# MainBoard.net
KiCad netlist of a schematic drawn in Altium Designer
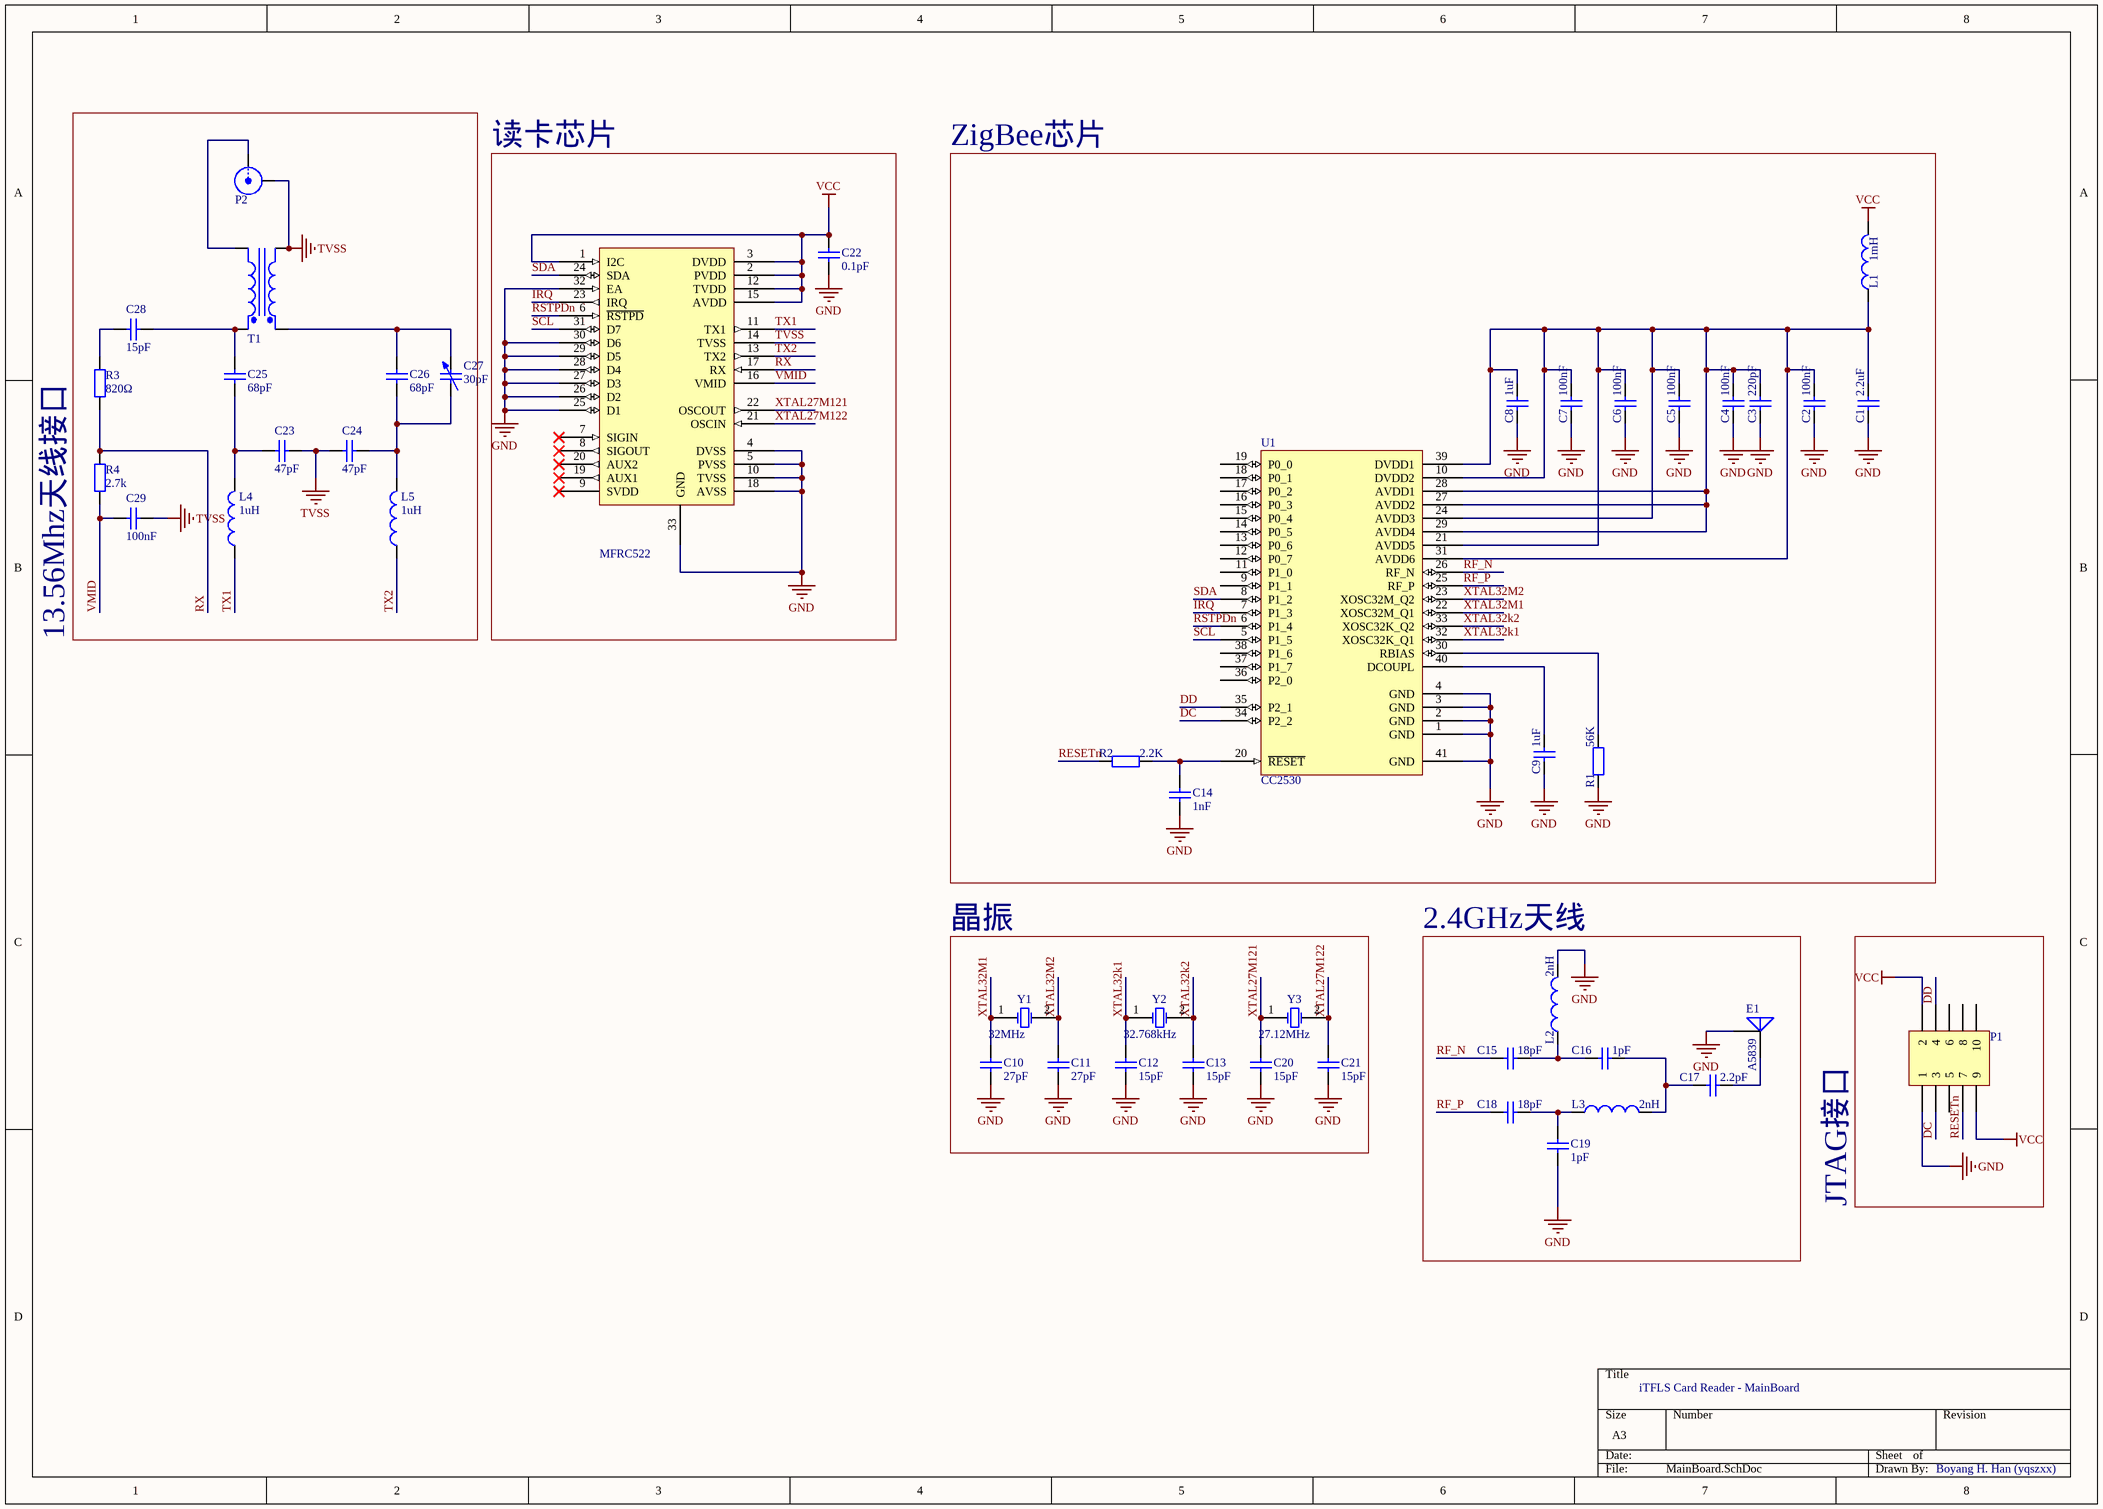
[diagram p0: MainBoard.SchDoc]

(export (version "E")
  (design (tool "Eeschema 10.0.6"))
  (components
    (comp (ref "C1")
      (value "2.2uF")
      (footprint "0603")
      (description "Capacitor")
      (fields (field (name "Comment") "Cap") (field (name "PUBLISHER") "Altium Limited"))
      (libsource (lib "Miscellaneous Devices") (part "Cap"))
    )
    (comp (ref "C2")
      (value "100nF")
      (footprint "0603")
      (description "Capacitor")
      (fields (field (name "Comment") "Cap") (field (name "PUBLISHER") "Altium Limited"))
      (libsource (lib "Miscellaneous Devices") (part "Cap"))
    )
    (comp (ref "C3")
      (value "220pF")
      (footprint "0603")
      (description "Capacitor")
      (fields (field (name "Comment") "Cap") (field (name "PUBLISHER") "Altium Limited"))
      (libsource (lib "Miscellaneous Devices") (part "Cap"))
    )
    (comp (ref "C4")
      (value "100nF")
      (footprint "0603")
      (description "Capacitor")
      (fields (field (name "Comment") "Cap") (field (name "PUBLISHER") "Altium Limited"))
      (libsource (lib "Miscellaneous Devices") (part "Cap"))
    )
    (comp (ref "C5")
      (value "100nF")
      (footprint "0603")
      (description "Capacitor")
      (fields (field (name "Comment") "Cap") (field (name "PUBLISHER") "Altium Limited"))
      (libsource (lib "Miscellaneous Devices") (part "Cap"))
    )
    (comp (ref "C6")
      (value "100nF")
      (footprint "0603")
      (description "Capacitor")
      (fields (field (name "Comment") "Cap") (field (name "PUBLISHER") "Altium Limited"))
      (libsource (lib "Miscellaneous Devices") (part "Cap"))
    )
    (comp (ref "C7")
      (value "100nF")
      (footprint "0603")
      (description "Capacitor")
      (fields (field (name "Comment") "Cap") (field (name "PUBLISHER") "Altium Limited"))
      (libsource (lib "Miscellaneous Devices") (part "Cap"))
    )
    (comp (ref "C8")
      (value "1uF")
      (footprint "0603")
      (description "Capacitor")
      (fields (field (name "Comment") "Cap") (field (name "PUBLISHER") "Altium Limited"))
      (libsource (lib "Miscellaneous Devices") (part "Cap"))
    )
    (comp (ref "C9")
      (value "1uF")
      (footprint "0603")
      (description "Capacitor")
      (fields (field (name "Comment") "Cap") (field (name "PUBLISHER") "Altium Limited"))
      (libsource (lib "Miscellaneous Devices") (part "Cap"))
    )
    (comp (ref "C10")
      (value "27pF")
      (footprint "0603")
      (description "Capacitor")
      (fields (field (name "Comment") "Cap") (field (name "PUBLISHER") "Altium Limited"))
      (libsource (lib "Miscellaneous Devices") (part "Cap"))
    )
    (comp (ref "C11")
      (value "27pF")
      (footprint "0603")
      (description "Capacitor")
      (fields (field (name "Comment") "Cap") (field (name "PUBLISHER") "Altium Limited"))
      (libsource (lib "Miscellaneous Devices") (part "Cap"))
    )
    (comp (ref "C12")
      (value "15pF")
      (footprint "0603")
      (description "Capacitor")
      (fields (field (name "Comment") "Cap") (field (name "PUBLISHER") "Altium Limited"))
      (libsource (lib "Miscellaneous Devices") (part "Cap"))
    )
    (comp (ref "C13")
      (value "15pF")
      (footprint "0603")
      (description "Capacitor")
      (fields (field (name "Comment") "Cap") (field (name "PUBLISHER") "Altium Limited"))
      (libsource (lib "Miscellaneous Devices") (part "Cap"))
    )
    (comp (ref "C14")
      (value "1nF")
      (footprint "0603")
      (description "Capacitor")
      (fields (field (name "Comment") "Cap") (field (name "PUBLISHER") "Altium Limited"))
      (libsource (lib "Miscellaneous Devices") (part "Cap"))
    )
    (comp (ref "C15")
      (value "18pF")
      (footprint "0603")
      (description "Capacitor")
      (fields (field (name "Comment") "Cap") (field (name "PUBLISHER") "Altium Limited"))
      (libsource (lib "Miscellaneous Devices") (part "Cap"))
    )
    (comp (ref "C16")
      (value "1pF")
      (footprint "0603")
      (description "Capacitor")
      (fields (field (name "Comment") "Cap") (field (name "PUBLISHER") "Altium Limited"))
      (libsource (lib "Miscellaneous Devices") (part "Cap"))
    )
    (comp (ref "C17")
      (value "2.2pF")
      (footprint "0603")
      (description "Capacitor")
      (fields (field (name "Comment") "Cap") (field (name "PUBLISHER") "Altium Limited"))
      (libsource (lib "Miscellaneous Devices") (part "Cap"))
    )
    (comp (ref "C18")
      (value "18pF")
      (footprint "0603")
      (description "Capacitor")
      (fields (field (name "Comment") "Cap") (field (name "PUBLISHER") "Altium Limited"))
      (libsource (lib "Miscellaneous Devices") (part "Cap"))
    )
    (comp (ref "C19")
      (value "1pF")
      (footprint "0603")
      (description "Capacitor")
      (fields (field (name "Comment") "Cap") (field (name "PUBLISHER") "Altium Limited"))
      (libsource (lib "Miscellaneous Devices") (part "Cap"))
    )
    (comp (ref "C20")
      (value "15pF")
      (footprint "0603")
      (description "Capacitor")
      (fields (field (name "Comment") "Cap") (field (name "PUBLISHER") "Altium Limited"))
      (libsource (lib "Miscellaneous Devices") (part "Cap"))
    )
    (comp (ref "C21")
      (value "15pF")
      (footprint "0603")
      (description "Capacitor")
      (fields (field (name "Comment") "Cap") (field (name "PUBLISHER") "Altium Limited"))
      (libsource (lib "Miscellaneous Devices") (part "Cap"))
    )
    (comp (ref "C22")
      (value "0.1pF")
      (footprint "0603")
      (description "Capacitor")
      (fields (field (name "Comment") "Cap") (field (name "PUBLISHER") "Altium Limited"))
      (libsource (lib "Miscellaneous Devices") (part "Cap"))
    )
    (comp (ref "C23")
      (value "47pF")
      (footprint "0603")
      (description "Capacitor")
      (fields (field (name "Comment") "Cap") (field (name "PUBLISHER") "Altium Limited"))
      (libsource (lib "Miscellaneous Devices") (part "Cap"))
    )
    (comp (ref "C24")
      (value "47pF")
      (footprint "0603")
      (description "Capacitor")
      (fields (field (name "Comment") "Cap") (field (name "PUBLISHER") "Altium Limited"))
      (libsource (lib "Miscellaneous Devices") (part "Cap"))
    )
    (comp (ref "C25")
      (value "68pF")
      (footprint "0603")
      (description "Capacitor")
      (fields (field (name "Comment") "Cap") (field (name "PUBLISHER") "Altium Limited"))
      (libsource (lib "Miscellaneous Devices") (part "Cap"))
    )
    (comp (ref "C26")
      (value "68pF")
      (footprint "0603")
      (description "Capacitor")
      (fields (field (name "Comment") "Cap") (field (name "PUBLISHER") "Altium Limited"))
      (libsource (lib "Miscellaneous Devices") (part "Cap"))
    )
    (comp (ref "C27")
      (value "30pF")
      (footprint "4x4VC")
      (description "Variable or Adjustable Capacitor")
      (fields (field (name "Comment") "Cap Var") (field (name "PUBLISHER") "Altium Limited"))
      (libsource (lib "Miscellaneous Devices") (part "Cap Var"))
    )
    (comp (ref "C28")
      (value "15pF")
      (footprint "0603")
      (description "Capacitor")
      (fields (field (name "Comment") "Cap") (field (name "PUBLISHER") "Altium Limited"))
      (libsource (lib "Miscellaneous Devices") (part "Cap"))
    )
    (comp (ref "C29")
      (value "100nF")
      (footprint "0603")
      (description "Capacitor")
      (fields (field (name "Comment") "Cap") (field (name "PUBLISHER") "Altium Limited"))
      (libsource (lib "Miscellaneous Devices") (part "Cap"))
    )
    (comp (ref "E1") (value "A5839") (footprint "A5839") (libsource (lib "A5839") (part "A5839")))
    (comp (ref "L1")
      (value "1mH")
      (footprint "0603")
      (description "Inductor")
      (fields (field (name "PUBLISHER") "Altium Limited"))
      (libsource (lib "Miscellaneous Devices") (part "Inductor"))
    )
    (comp (ref "L2")
      (value "2nH")
      (footprint "0603")
      (description "Inductor")
      (fields (field (name "PUBLISHER") "Altium Limited"))
      (libsource (lib "Miscellaneous Devices") (part "Inductor"))
    )
    (comp (ref "L3")
      (value "2nH")
      (footprint "0603")
      (description "Inductor")
      (fields (field (name "PUBLISHER") "Altium Limited"))
      (libsource (lib "Miscellaneous Devices") (part "Inductor"))
    )
    (comp (ref "L4")
      (value "1uH")
      (footprint "0603")
      (description "Inductor")
      (fields (field (name "PUBLISHER") "Altium Limited"))
      (libsource (lib "Miscellaneous Devices") (part "Inductor"))
    )
    (comp (ref "L5")
      (value "1uH")
      (footprint "0603")
      (description "Inductor")
      (fields (field (name "PUBLISHER") "Altium Limited"))
      (libsource (lib "Miscellaneous Devices") (part "Inductor"))
    )
    (comp (ref "P1")
      (value "Header 5X2")
      (footprint "HDR2X5")
      (description "Header, 5-Pin, Dual row")
      (fields (field (name "PUBLISHER") "Altium Limited"))
      (libsource (lib "Miscellaneous Connectors") (part "Header 5X2"))
    )
    (comp (ref "P2")
      (value "U.FL")
      (footprint "U.FL")
      (description "SMB Straight Connector")
      (fields (field (name "PUBLISHER") "Altium Limited"))
      (libsource (lib "Miscellaneous Connectors") (part "SMB"))
    )
    (comp (ref "R1")
      (value "56K")
      (footprint "0603")
      (description "Resistor")
      (fields (field (name "Comment") "Res2") (field (name "PUBLISHER") "Altium Limited"))
      (libsource (lib "Miscellaneous Devices") (part "Res2"))
    )
    (comp (ref "R2")
      (value "2.2K")
      (footprint "0603")
      (description "Resistor")
      (fields (field (name "Comment") "Res2") (field (name "PUBLISHER") "Altium Limited"))
      (libsource (lib "") (part "Res2_1"))
    )
    (comp (ref "R3")
      (value "820Ω")
      (footprint "0603")
      (description "Resistor")
      (fields (field (name "Comment") "Res2") (field (name "PUBLISHER") "Altium Limited"))
      (libsource (lib "Miscellaneous Devices") (part "Res2"))
    )
    (comp (ref "R4")
      (value "2.7k")
      (footprint "0603")
      (description "Resistor")
      (fields (field (name "Comment") "Res2") (field (name "PUBLISHER") "Altium Limited"))
      (libsource (lib "Miscellaneous Devices") (part "Res2"))
    )
    (comp (ref "T1")
      (value "1812WBT-3")
      (footprint "1812WBT-3")
      (libsource (lib "Coilcraft 1812WBT-3") (part "1812WBT-3"))
    )
    (comp (ref "U1") (value "CC2530") (footprint "QFN40") (libsource (lib "CC2530") (part "CC2530")))
    (comp (ref "U2") (value "MFRC522") (footprint "QFN32") (libsource (lib "MFRC522") (part "MFRC522")))
    (comp (ref "Y1")
      (value "32MHz")
      (footprint "XTAL3225")
      (description "Crystal Oscillator")
      (fields (field (name "Comment") "XTAL") (field (name "PUBLISHER") "Altium Limited"))
      (libsource (lib "Miscellaneous Devices") (part "XTAL"))
    )
    (comp (ref "Y2")
      (value "32.768kHz")
      (footprint "XTAL3215")
      (description "Crystal Oscillator")
      (fields (field (name "Comment") "XTAL") (field (name "PUBLISHER") "Altium Limited"))
      (libsource (lib "Miscellaneous Devices") (part "XTAL"))
    )
    (comp (ref "Y3")
      (value "27.12MHz")
      (footprint "XTAL3225")
      (description "Crystal Oscillator")
      (fields (field (name "Comment") "XTAL") (field (name "PUBLISHER") "Altium Limited"))
      (libsource (lib "Miscellaneous Devices") (part "XTAL"))
    )
  )
  (nets
    (net (code "1") (name "/DC") (class "Default")
      (node (ref "P1") (pin "3") (pinfunction "3_3") (pintype "passive"))
      (node (ref "U1") (pin "34") (pinfunction "P2_2_34") (pintype "bidirectional"))
    )
    (net (code "2") (name "/DD") (class "Default")
      (node (ref "P1") (pin "4") (pinfunction "4_4") (pintype "passive"))
      (node (ref "U1") (pin "35") (pinfunction "P2_1_35") (pintype "bidirectional"))
    )
    (net (code "3") (name "/IRQ") (class "Default")
      (node (ref "U1") (pin "7") (pinfunction "P1_3_7") (pintype "bidirectional"))
      (node (ref "U2") (pin "23") (pinfunction "IRQ_23") (pintype "output"))
    )
    (net (code "4") (name "/RESETn") (class "Default")
      (node (ref "P1") (pin "7") (pinfunction "7_7") (pintype "passive"))
      (node (ref "R2") (pin "1") (pinfunction "1_1") (pintype "passive"))
    )
    (net (code "5") (name "/RF_N") (class "Default")
      (node (ref "C15") (pin "1") (pinfunction "1_1") (pintype "passive"))
      (node (ref "U1") (pin "26") (pinfunction "RF_N_26") (pintype "bidirectional"))
    )
    (net (code "6") (name "/RF_P") (class "Default")
      (node (ref "C18") (pin "1") (pinfunction "1_1") (pintype "passive"))
      (node (ref "U1") (pin "25") (pinfunction "RF_P_25") (pintype "bidirectional"))
    )
    (net (code "7") (name "/RSTPDn") (class "Default")
      (node (ref "U1") (pin "6") (pinfunction "P1_4_6") (pintype "bidirectional"))
      (node (ref "U2") (pin "6") (pinfunction "~{RSTPD}_6") (pintype "input"))
    )
    (net (code "8") (name "/RX") (class "Default")
      (node (ref "R3") (pin "1") (pinfunction "1_1") (pintype "passive"))
      (node (ref "R4") (pin "2") (pinfunction "2_2") (pintype "passive"))
      (node (ref "U2") (pin "17") (pinfunction "RX_17") (pintype "input"))
    )
    (net (code "9") (name "/SCL") (class "Default")
      (node (ref "U1") (pin "5") (pinfunction "P1_5_5") (pintype "bidirectional"))
      (node (ref "U2") (pin "31") (pinfunction "D7_31") (pintype "bidirectional"))
    )
    (net (code "10") (name "/SDA") (class "Default")
      (node (ref "U1") (pin "8") (pinfunction "P1_2_8") (pintype "bidirectional"))
      (node (ref "U2") (pin "24") (pinfunction "SDA_24") (pintype "bidirectional"))
    )
    (net (code "11") (name "/TX1") (class "Default")
      (node (ref "L4") (pin "1") (pinfunction "1_1") (pintype "passive"))
      (node (ref "U2") (pin "11") (pinfunction "TX1_11") (pintype "output"))
    )
    (net (code "12") (name "/TX2") (class "Default")
      (node (ref "L5") (pin "1") (pinfunction "1_1") (pintype "passive"))
      (node (ref "U2") (pin "13") (pinfunction "TX2_13") (pintype "output"))
    )
    (net (code "13") (name "/VMID") (class "Default")
      (node (ref "C29") (pin "2") (pinfunction "2_2") (pintype "passive"))
      (node (ref "R4") (pin "1") (pinfunction "1_1") (pintype "passive"))
      (node (ref "U2") (pin "16") (pinfunction "VMID_16") (pintype "power_in"))
    )
    (net (code "14") (name "/XTAL27M121") (class "Default")
      (node (ref "C20") (pin "2") (pinfunction "2_2") (pintype "passive"))
      (node (ref "U2") (pin "22") (pinfunction "OSCOUT_22") (pintype "output"))
      (node (ref "Y3") (pin "1") (pinfunction "OSC1_1") (pintype "passive"))
    )
    (net (code "15") (name "/XTAL27M122") (class "Default")
      (node (ref "C21") (pin "2") (pinfunction "2_2") (pintype "passive"))
      (node (ref "U2") (pin "21") (pinfunction "OSCIN_21") (pintype "input"))
      (node (ref "Y3") (pin "2") (pinfunction "OSC2_2") (pintype "passive"))
    )
    (net (code "16") (name "/XTAL32M1") (class "Default")
      (node (ref "C10") (pin "2") (pinfunction "2_2") (pintype "passive"))
      (node (ref "U1") (pin "22") (pinfunction "XOSC32M_Q1_22") (pintype "bidirectional"))
      (node (ref "Y1") (pin "1") (pinfunction "OSC1_1") (pintype "passive"))
    )
    (net (code "17") (name "/XTAL32M2") (class "Default")
      (node (ref "C11") (pin "2") (pinfunction "2_2") (pintype "passive"))
      (node (ref "U1") (pin "23") (pinfunction "XOSC32M_Q2_23") (pintype "bidirectional"))
      (node (ref "Y1") (pin "2") (pinfunction "OSC2_2") (pintype "passive"))
    )
    (net (code "18") (name "/XTAL32k1") (class "Default")
      (node (ref "C12") (pin "2") (pinfunction "2_2") (pintype "passive"))
      (node (ref "U1") (pin "32") (pinfunction "XOSC32K_Q1_32") (pintype "bidirectional"))
      (node (ref "Y2") (pin "1") (pinfunction "OSC1_1") (pintype "passive"))
    )
    (net (code "19") (name "/XTAL32k2") (class "Default")
      (node (ref "C13") (pin "2") (pinfunction "2_2") (pintype "passive"))
      (node (ref "U1") (pin "33") (pinfunction "XOSC32K_Q2_33") (pintype "bidirectional"))
      (node (ref "Y2") (pin "2") (pinfunction "OSC2_2") (pintype "passive"))
    )
    (net (code "20") (name "GND") (class "Default")
      (node (ref "C1") (pin "1") (pinfunction "1_1") (pintype "passive"))
      (node (ref "C10") (pin "1") (pinfunction "1_1") (pintype "passive"))
      (node (ref "C11") (pin "1") (pinfunction "1_1") (pintype "passive"))
      (node (ref "C12") (pin "1") (pinfunction "1_1") (pintype "passive"))
      (node (ref "C13") (pin "1") (pinfunction "1_1") (pintype "passive"))
      (node (ref "C14") (pin "1") (pinfunction "1_1") (pintype "passive"))
      (node (ref "C19") (pin "1") (pinfunction "1_1") (pintype "passive"))
      (node (ref "C2") (pin "1") (pinfunction "1_1") (pintype "passive"))
      (node (ref "C20") (pin "1") (pinfunction "1_1") (pintype "passive"))
      (node (ref "C21") (pin "1") (pinfunction "1_1") (pintype "passive"))
      (node (ref "C22") (pin "1") (pinfunction "1_1") (pintype "passive"))
      (node (ref "C3") (pin "1") (pinfunction "1_1") (pintype "passive"))
      (node (ref "C4") (pin "1") (pinfunction "1_1") (pintype "passive"))
      (node (ref "C5") (pin "1") (pinfunction "1_1") (pintype "passive"))
      (node (ref "C6") (pin "1") (pinfunction "1_1") (pintype "passive"))
      (node (ref "C7") (pin "1") (pinfunction "1_1") (pintype "passive"))
      (node (ref "C8") (pin "1") (pinfunction "1_1") (pintype "passive"))
      (node (ref "C9") (pin "1") (pinfunction "1_1") (pintype "passive"))
      (node (ref "E1") (pin "2") (pinfunction "GND_2") (pintype "passive"))
      (node (ref "L2") (pin "2") (pinfunction "2_2") (pintype "passive"))
      (node (ref "P1") (pin "1") (pinfunction "1_1") (pintype "passive"))
      (node (ref "R1") (pin "1") (pinfunction "1_1") (pintype "passive"))
      (node (ref "U1") (pin "1") (pinfunction "GND_1") (pintype "power_in"))
      (node (ref "U1") (pin "2") (pinfunction "GND_2") (pintype "power_in"))
      (node (ref "U1") (pin "3") (pinfunction "GND_3") (pintype "power_in"))
      (node (ref "U1") (pin "4") (pinfunction "GND_4") (pintype "power_in"))
      (node (ref "U1") (pin "41") (pinfunction "GND_41") (pintype "power_in"))
      (node (ref "U2") (pin "10") (pinfunction "TVSS_10") (pintype "power_in"))
      (node (ref "U2") (pin "18") (pinfunction "AVSS_18") (pintype "power_in"))
      (node (ref "U2") (pin "25") (pinfunction "D1_25") (pintype "bidirectional"))
      (node (ref "U2") (pin "26") (pinfunction "D2_26") (pintype "bidirectional"))
      (node (ref "U2") (pin "27") (pinfunction "D3_27") (pintype "bidirectional"))
      (node (ref "U2") (pin "28") (pinfunction "D4_28") (pintype "bidirectional"))
      (node (ref "U2") (pin "29") (pinfunction "D5_29") (pintype "bidirectional"))
      (node (ref "U2") (pin "30") (pinfunction "D6_30") (pintype "bidirectional"))
      (node (ref "U2") (pin "32") (pinfunction "EA_32") (pintype "input"))
      (node (ref "U2") (pin "33") (pinfunction "GND_33") (pintype "power_in"))
      (node (ref "U2") (pin "4") (pinfunction "DVSS_4") (pintype "power_in"))
      (node (ref "U2") (pin "5") (pinfunction "PVSS_5") (pintype "power_in"))
    )
    (net (code "21") (name "Net-(C15-Pad2)") (class "Default")
      (node (ref "C15") (pin "2") (pinfunction "2_2") (pintype "passive"))
      (node (ref "C16") (pin "1") (pinfunction "1_1") (pintype "passive"))
      (node (ref "L2") (pin "1") (pinfunction "1_1") (pintype "passive"))
    )
    (net (code "22") (name "Net-(C16-Pad2)") (class "Default")
      (node (ref "C16") (pin "2") (pinfunction "2_2") (pintype "passive"))
      (node (ref "C17") (pin "1") (pinfunction "1_1") (pintype "passive"))
      (node (ref "L3") (pin "2") (pinfunction "2_2") (pintype "passive"))
    )
    (net (code "23") (name "Net-(C18-Pad2)") (class "Default")
      (node (ref "C18") (pin "2") (pinfunction "2_2") (pintype "passive"))
      (node (ref "C19") (pin "2") (pinfunction "2_2") (pintype "passive"))
      (node (ref "L3") (pin "1") (pinfunction "1_1") (pintype "passive"))
    )
    (net (code "24") (name "Net-(C23-Pad2)") (class "Default")
      (node (ref "C23") (pin "2") (pinfunction "2_2") (pintype "passive"))
      (node (ref "C25") (pin "1") (pinfunction "1_1") (pintype "passive"))
      (node (ref "L4") (pin "2") (pinfunction "2_2") (pintype "passive"))
    )
    (net (code "25") (name "Net-(C24-Pad1)") (class "Default")
      (node (ref "C24") (pin "1") (pinfunction "1_1") (pintype "passive"))
      (node (ref "C26") (pin "1") (pinfunction "1_1") (pintype "passive"))
      (node (ref "C27") (pin "1") (pinfunction "1_1") (pintype "passive"))
      (node (ref "L5") (pin "2") (pinfunction "2_2") (pintype "passive"))
    )
    (net (code "26") (name "Net-(C28-Pad2)") (class "Default")
      (node (ref "C28") (pin "2") (pinfunction "2_2") (pintype "passive"))
      (node (ref "R3") (pin "2") (pinfunction "2_2") (pintype "passive"))
    )
    (net (code "27") (name "Net-(E1-FEED)") (class "Default")
      (node (ref "C17") (pin "2") (pinfunction "2_2") (pintype "passive"))
      (node (ref "E1") (pin "1") (pinfunction "FEED_1") (pintype "passive"))
    )
    (net (code "28") (name "Net-(P2-X)") (class "Default")
      (node (ref "P2") (pin "1") (pinfunction "X_1") (pintype "passive"))
      (node (ref "T1") (pin "3") (pinfunction "Sec-_3") (pintype "passive"))
    )
    (net (code "29") (name "Net-(T1-Pri+)") (class "Default")
      (node (ref "C26") (pin "2") (pinfunction "2_2") (pintype "passive"))
      (node (ref "C27") (pin "2") (pinfunction "2_2") (pintype "passive"))
      (node (ref "T1") (pin "1") (pinfunction "Pri+_1") (pintype "passive"))
    )
    (net (code "30") (name "Net-(T1-Sec+)") (class "Default")
      (node (ref "C25") (pin "2") (pinfunction "2_2") (pintype "passive"))
      (node (ref "C28") (pin "1") (pinfunction "1_1") (pintype "passive"))
      (node (ref "T1") (pin "4") (pinfunction "Sec+_4") (pintype "passive"))
    )
    (net (code "31") (name "Net-(U1-AVDD1)") (class "Default")
      (node (ref "C1") (pin "2") (pinfunction "2_2") (pintype "passive"))
      (node (ref "C2") (pin "2") (pinfunction "2_2") (pintype "passive"))
      (node (ref "C3") (pin "2") (pinfunction "2_2") (pintype "passive"))
      (node (ref "C4") (pin "2") (pinfunction "2_2") (pintype "passive"))
      (node (ref "C5") (pin "2") (pinfunction "2_2") (pintype "passive"))
      (node (ref "C6") (pin "2") (pinfunction "2_2") (pintype "passive"))
      (node (ref "C7") (pin "2") (pinfunction "2_2") (pintype "passive"))
      (node (ref "C8") (pin "2") (pinfunction "2_2") (pintype "passive"))
      (node (ref "L1") (pin "1") (pinfunction "1_1") (pintype "passive"))
      (node (ref "U1") (pin "10") (pinfunction "DVDD2_10") (pintype "power_in"))
      (node (ref "U1") (pin "21") (pinfunction "AVDD5_21") (pintype "power_in"))
      (node (ref "U1") (pin "24") (pinfunction "AVDD3_24") (pintype "power_in"))
      (node (ref "U1") (pin "27") (pinfunction "AVDD2_27") (pintype "power_in"))
      (node (ref "U1") (pin "28") (pinfunction "AVDD1_28") (pintype "power_in"))
      (node (ref "U1") (pin "29") (pinfunction "AVDD4_29") (pintype "power_in"))
      (node (ref "U1") (pin "31") (pinfunction "AVDD6_31") (pintype "power_in"))
      (node (ref "U1") (pin "39") (pinfunction "DVDD1_39") (pintype "power_in"))
    )
    (net (code "32") (name "Net-(U1-DCOUPL)") (class "Default")
      (node (ref "C9") (pin "2") (pinfunction "2_2") (pintype "passive"))
      (node (ref "U1") (pin "40") (pinfunction "DCOUPL_40") (pintype "power_in"))
    )
    (net (code "33") (name "Net-(U1-RBIAS)") (class "Default")
      (node (ref "R1") (pin "2") (pinfunction "2_2") (pintype "passive"))
      (node (ref "U1") (pin "30") (pinfunction "RBIAS_30") (pintype "bidirectional"))
    )
    (net (code "34") (name "Net-(U1-~{RESET})") (class "Default")
      (node (ref "C14") (pin "2") (pinfunction "2_2") (pintype "passive"))
      (node (ref "R2") (pin "2") (pinfunction "2_2") (pintype "passive"))
      (node (ref "U1") (pin "20") (pinfunction "~{RESET}_20") (pintype "input"))
    )
    (net (code "35") (name "TVSS") (class "Default")
      (node (ref "C23") (pin "1") (pinfunction "1_1") (pintype "passive"))
      (node (ref "C24") (pin "2") (pinfunction "2_2") (pintype "passive"))
      (node (ref "C29") (pin "1") (pinfunction "1_1") (pintype "passive"))
      (node (ref "P2") (pin "2") (pinfunction "Y_2") (pintype "passive"))
      (node (ref "T1") (pin "2") (pinfunction "Pri-_2") (pintype "passive"))
      (node (ref "U2") (pin "14") (pinfunction "TVSS_14") (pintype "power_in"))
    )
    (net (code "36") (name "VCC") (class "Default")
      (node (ref "C22") (pin "2") (pinfunction "2_2") (pintype "passive"))
      (node (ref "L1") (pin "2") (pinfunction "2_2") (pintype "passive"))
      (node (ref "P1") (pin "2") (pinfunction "2_2") (pintype "passive"))
      (node (ref "P1") (pin "9") (pinfunction "9_9") (pintype "passive"))
      (node (ref "U2") (pin "1") (pinfunction "I2C_1") (pintype "input"))
      (node (ref "U2") (pin "12") (pinfunction "TVDD_12") (pintype "power_in"))
      (node (ref "U2") (pin "15") (pinfunction "AVDD_15") (pintype "power_in"))
      (node (ref "U2") (pin "2") (pinfunction "PVDD_2") (pintype "power_in"))
      (node (ref "U2") (pin "3") (pinfunction "DVDD_3") (pintype "power_in"))
    )
    (net (code "37") (name "unconnected-(P1-Pad5)") (class "Default")
      (node (ref "P1") (pin "5") (pinfunction "5_5") (pintype "passive"))
    )
    (net (code "38") (name "unconnected-(P1-Pad6)") (class "Default")
      (node (ref "P1") (pin "6") (pinfunction "6_6") (pintype "passive"))
    )
    (net (code "39") (name "unconnected-(P1-Pad8)") (class "Default")
      (node (ref "P1") (pin "8") (pinfunction "8_8") (pintype "passive"))
    )
    (net (code "40") (name "unconnected-(P1-Pad10)") (class "Default")
      (node (ref "P1") (pin "10") (pinfunction "10_10") (pintype "passive"))
    )
    (net (code "41") (name "unconnected-(U1-P0_0-Pad19)") (class "Default")
      (node (ref "U1") (pin "19") (pinfunction "P0_0_19") (pintype "bidirectional"))
    )
    (net (code "42") (name "unconnected-(U1-P0_1-Pad18)") (class "Default")
      (node (ref "U1") (pin "18") (pinfunction "P0_1_18") (pintype "bidirectional"))
    )
    (net (code "43") (name "unconnected-(U1-P0_2-Pad17)") (class "Default")
      (node (ref "U1") (pin "17") (pinfunction "P0_2_17") (pintype "bidirectional"))
    )
    (net (code "44") (name "unconnected-(U1-P0_3-Pad16)") (class "Default")
      (node (ref "U1") (pin "16") (pinfunction "P0_3_16") (pintype "bidirectional"))
    )
    (net (code "45") (name "unconnected-(U1-P0_4-Pad15)") (class "Default")
      (node (ref "U1") (pin "15") (pinfunction "P0_4_15") (pintype "bidirectional"))
    )
    (net (code "46") (name "unconnected-(U1-P0_5-Pad14)") (class "Default")
      (node (ref "U1") (pin "14") (pinfunction "P0_5_14") (pintype "bidirectional"))
    )
    (net (code "47") (name "unconnected-(U1-P0_6-Pad13)") (class "Default")
      (node (ref "U1") (pin "13") (pinfunction "P0_6_13") (pintype "bidirectional"))
    )
    (net (code "48") (name "unconnected-(U1-P0_7-Pad12)") (class "Default")
      (node (ref "U1") (pin "12") (pinfunction "P0_7_12") (pintype "bidirectional"))
    )
    (net (code "49") (name "unconnected-(U1-P1_0-Pad11)") (class "Default")
      (node (ref "U1") (pin "11") (pinfunction "P1_0_11") (pintype "bidirectional"))
    )
    (net (code "50") (name "unconnected-(U1-P1_1-Pad9)") (class "Default")
      (node (ref "U1") (pin "9") (pinfunction "P1_1_9") (pintype "bidirectional"))
    )
    (net (code "51") (name "unconnected-(U1-P1_6-Pad38)") (class "Default")
      (node (ref "U1") (pin "38") (pinfunction "P1_6_38") (pintype "bidirectional"))
    )
    (net (code "52") (name "unconnected-(U1-P1_7-Pad37)") (class "Default")
      (node (ref "U1") (pin "37") (pinfunction "P1_7_37") (pintype "bidirectional"))
    )
    (net (code "53") (name "unconnected-(U1-P2_0-Pad36)") (class "Default")
      (node (ref "U1") (pin "36") (pinfunction "P2_0_36") (pintype "bidirectional"))
    )
    (net (code "54") (name "unconnected-(U2-AUX1-Pad19)") (class "Default")
      (node (ref "U2") (pin "19") (pinfunction "AUX1_19") (pintype "output+no_connect"))
    )
    (net (code "55") (name "unconnected-(U2-AUX2-Pad20)") (class "Default")
      (node (ref "U2") (pin "20") (pinfunction "AUX2_20") (pintype "output+no_connect"))
    )
    (net (code "56") (name "unconnected-(U2-SIGIN-Pad7)") (class "Default")
      (node (ref "U2") (pin "7") (pinfunction "SIGIN_7") (pintype "input+no_connect"))
    )
    (net (code "57") (name "unconnected-(U2-SIGOUT-Pad8)") (class "Default")
      (node (ref "U2") (pin "8") (pinfunction "SIGOUT_8") (pintype "output+no_connect"))
    )
    (net (code "58") (name "unconnected-(U2-SVDD-Pad9)") (class "Default")
      (node (ref "U2") (pin "9") (pinfunction "SVDD_9") (pintype "power_in+no_connect"))
    )
  )
)
